# HeaterControl.net
KiCad netlist of a schematic drawn in EAGLE
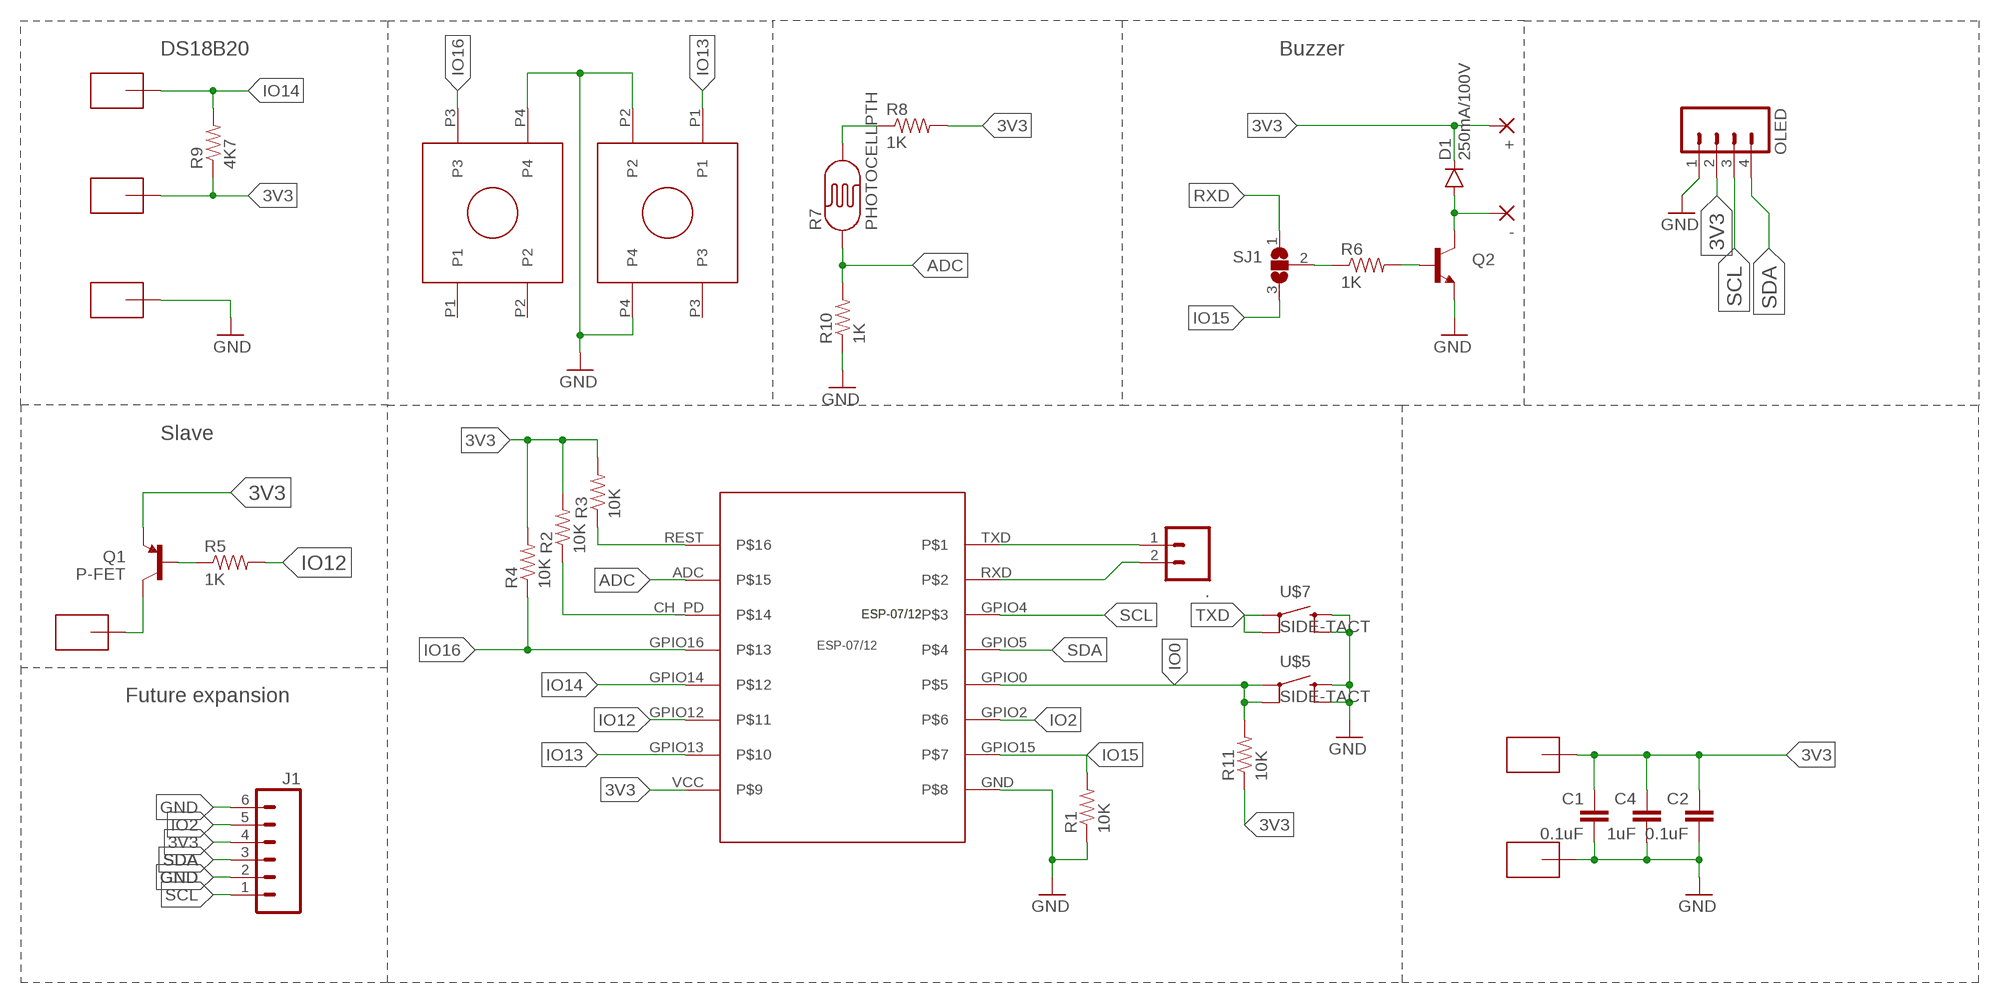
[diagram p0: schematic, sheet 1]

(export (version "E")
  (design (tool "Eeschema 10.0.6"))
  (components
    (comp (ref "+")
      (value "1,6/0,8")
      (footprint "eagle-import:1,6_0,8")
      (libsource (lib "eagle-import") (part "1,6/0,8"))
    )
    (comp (ref "-")
      (value "1,6/0,8")
      (footprint "eagle-import:1,6_0,8")
      (libsource (lib "eagle-import") (part "1,6/0,8"))
    )
    (comp (ref ".")
      (value "M02PTH")
      (footprint "eagle-import:1X02")
      (libsource (lib "eagle-import") (part "M02PTH"))
    )
    (comp (ref "C1")
      (value "0.1uF")
      (footprint "eagle-import:0805-CAP")
      (libsource (lib "eagle-import") (part "CAP"))
    )
    (comp (ref "C2")
      (value "0.1uF")
      (footprint "eagle-import:0805-CAP")
      (libsource (lib "eagle-import") (part "CAP"))
    )
    (comp (ref "C4")
      (value "1uF")
      (footprint "eagle-import:0805-CAP")
      (libsource (lib "eagle-import") (part "CAP"))
    )
    (comp (ref "D1")
      (value "250mA/100V")
      (footprint "eagle-import:SOD-323")
      (libsource (lib "eagle-import") (part "DIODEBAS16"))
    )
    (comp (ref "J1")
      (value "M06SILK_FEMALE_PTH")
      (footprint "eagle-import:1X06")
      (libsource (lib "eagle-import") (part "M06SILK_FEMALE_PTH"))
    )
    (comp (ref "LEFT")
      (value "OMROM_TH")
      (footprint "eagle-import:OMROM_TH")
      (libsource (lib "eagle-import") (part "OMROM_TH"))
    )
    (comp (ref "OLED")
      (value "M04PTH")
      (footprint "eagle-import:1X04")
      (libsource (lib "eagle-import") (part "M04PTH"))
    )
    (comp (ref "Q1")
      (value "P-FET")
      (footprint "eagle-import:SOT23-3")
      (libsource (lib "eagle-import") (part "TRANSISTOR_PNPSMD"))
    )
    (comp (ref "Q2")
      (value "TRANSISTOR_NPNSOT23-3")
      (footprint "eagle-import:SOT23-3")
      (libsource (lib "eagle-import") (part "TRANSISTOR_NPNSOT23-3"))
    )
    (comp (ref "R1")
      (value "10K")
      (footprint "eagle-import:0805")
      (libsource (lib "eagle-import") (part "RESISTOR0805-RES"))
    )
    (comp (ref "R2")
      (value "10K")
      (footprint "eagle-import:0805")
      (libsource (lib "eagle-import") (part "RESISTOR0805-RES"))
    )
    (comp (ref "R3")
      (value "10K")
      (footprint "eagle-import:0805")
      (libsource (lib "eagle-import") (part "RESISTOR0805-RES"))
    )
    (comp (ref "R4")
      (value "10K")
      (footprint "eagle-import:0805")
      (libsource (lib "eagle-import") (part "RESISTOR0805-RES"))
    )
    (comp (ref "R5")
      (value "1K")
      (footprint "eagle-import:0805")
      (libsource (lib "eagle-import") (part "RESISTOR0805-RES"))
    )
    (comp (ref "R6")
      (value "1K")
      (footprint "eagle-import:0805")
      (libsource (lib "eagle-import") (part "RESISTOR0805-RES"))
    )
    (comp (ref "R7")
      (value "PHOTOCELLPTH")
      (footprint "eagle-import:PHOTOCELL")
      (libsource (lib "eagle-import") (part "PHOTOCELLPTH"))
    )
    (comp (ref "R8")
      (value "1K")
      (footprint "eagle-import:0805")
      (libsource (lib "eagle-import") (part "RESISTOR0805-RES"))
    )
    (comp (ref "R9")
      (value "4K7")
      (footprint "eagle-import:0805")
      (libsource (lib "eagle-import") (part "RESISTOR0805-RES"))
    )
    (comp (ref "R10")
      (value "1K")
      (footprint "eagle-import:0805")
      (libsource (lib "eagle-import") (part "RESISTOR0805-RES"))
    )
    (comp (ref "R11")
      (value "10K")
      (footprint "eagle-import:0805")
      (libsource (lib "eagle-import") (part "RESISTOR0805-RES"))
    )
    (comp (ref "RIGHT")
      (value "OMROM_TH")
      (footprint "eagle-import:OMROM_TH")
      (libsource (lib "eagle-import") (part "OMROM_TH"))
    )
    (comp (ref "SJ1")
      (value "SJ2W")
      (footprint "eagle-import:SJ_2")
      (libsource (lib "eagle-import") (part "SJ2W"))
    )
    (comp (ref "U$1")
      (value "ESP-07/12")
      (footprint "eagle-import:ESP-07_12")
      (libsource (lib "eagle-import") (part "ESP-07/12"))
    )
    (comp (ref "U$2")
      (value "SMD-PAD1")
      (footprint "eagle-import:SMD-PAD1")
      (libsource (lib "eagle-import") (part "SMD-PAD1"))
    )
    (comp (ref "U$3")
      (value "SMD-PAD1")
      (footprint "eagle-import:SMD-PAD1")
      (libsource (lib "eagle-import") (part "SMD-PAD1"))
    )
    (comp (ref "U$5")
      (value "SIDE-TACT")
      (footprint "eagle-import:SIDE-TACT")
      (libsource (lib "eagle-import") (part "SIDE-TACT"))
    )
    (comp (ref "U$6")
      (value "SMD-PAD1")
      (footprint "eagle-import:SMD-PAD1")
      (libsource (lib "eagle-import") (part "SMD-PAD1"))
    )
    (comp (ref "U$7")
      (value "SIDE-TACT")
      (footprint "eagle-import:SIDE-TACT")
      (libsource (lib "eagle-import") (part "SIDE-TACT"))
    )
    (comp (ref "U$8")
      (value "SMD-PAD1")
      (footprint "eagle-import:SMD-PAD1")
      (libsource (lib "eagle-import") (part "SMD-PAD1"))
    )
    (comp (ref "U$10")
      (value "SMD-PAD1")
      (footprint "eagle-import:SMD-PAD1")
      (libsource (lib "eagle-import") (part "SMD-PAD1"))
    )
    (comp (ref "U$11")
      (value "SMD-PAD1")
      (footprint "eagle-import:SMD-PAD1")
      (libsource (lib "eagle-import") (part "SMD-PAD1"))
    )
  )
  (nets
    (net (code "1") (name "3V3") (class "Default")
      (node (ref "+") (pin "1") (pinfunction "P_1") (pintype "passive"))
      (node (ref "C1") (pin "1") (pinfunction "1_1") (pintype "passive"))
      (node (ref "C2") (pin "1") (pinfunction "1_1") (pintype "passive"))
      (node (ref "C4") (pin "1") (pinfunction "1_1") (pintype "passive"))
      (node (ref "D1") (pin "C") (pinfunction "C_C") (pintype "passive"))
      (node (ref "J1") (pin "4") (pinfunction "4_4") (pintype "passive"))
      (node (ref "OLED") (pin "2") (pinfunction "2_2") (pintype "passive"))
      (node (ref "Q1") (pin "2") (pinfunction "E_2") (pintype "passive"))
      (node (ref "R11") (pin "1") (pinfunction "1_1") (pintype "passive"))
      (node (ref "R2") (pin "2") (pinfunction "2_2") (pintype "passive"))
      (node (ref "R3") (pin "2") (pinfunction "2_2") (pintype "passive"))
      (node (ref "R4") (pin "2") (pinfunction "2_2") (pintype "passive"))
      (node (ref "R8") (pin "2") (pinfunction "2_2") (pintype "passive"))
      (node (ref "R9") (pin "1") (pinfunction "1_1") (pintype "passive"))
      (node (ref "U$1") (pin "VCC") (pinfunction "P$9_VCC") (pintype "bidirectional"))
      (node (ref "U$3") (pin ">NAME") (pinfunction "P$1_>NAME") (pintype "bidirectional"))
      (node (ref "U$8") (pin ">NAME") (pinfunction "P$1_>NAME") (pintype "bidirectional"))
    )
    (net (code "2") (name "ADC") (class "Default")
      (node (ref "R10") (pin "2") (pinfunction "2_2") (pintype "passive"))
      (node (ref "R7") (pin "1") (pinfunction "P$1_1") (pintype "bidirectional"))
      (node (ref "U$1") (pin "ADC") (pinfunction "P$15_ADC") (pintype "bidirectional"))
    )
    (net (code "3") (name "GND") (class "Default")
      (node (ref "C1") (pin "2") (pinfunction "2_2") (pintype "passive"))
      (node (ref "C2") (pin "2") (pinfunction "2_2") (pintype "passive"))
      (node (ref "C4") (pin "2") (pinfunction "2_2") (pintype "passive"))
      (node (ref "J1") (pin "2") (pinfunction "2_2") (pintype "passive"))
      (node (ref "J1") (pin "6") (pinfunction "6_6") (pintype "passive"))
      (node (ref "LEFT") (pin "P4") (pinfunction "P4_P4") (pintype "bidirectional"))
      (node (ref "OLED") (pin "1") (pinfunction "1_1") (pintype "passive"))
      (node (ref "Q2") (pin "2") (pinfunction "E_2") (pintype "passive"))
      (node (ref "R1") (pin "1") (pinfunction "1_1") (pintype "passive"))
      (node (ref "R10") (pin "1") (pinfunction "1_1") (pintype "passive"))
      (node (ref "RIGHT") (pin "P2") (pinfunction "P2_P2") (pintype "bidirectional"))
      (node (ref "RIGHT") (pin "P4") (pinfunction "P4_P4") (pintype "bidirectional"))
      (node (ref "U$1") (pin "GND") (pinfunction "P$8_GND") (pintype "bidirectional"))
      (node (ref "U$11") (pin ">NAME") (pinfunction "P$1_>NAME") (pintype "bidirectional"))
      (node (ref "U$5") (pin "3") (pinfunction "2_3") (pintype "passive"))
      (node (ref "U$5") (pin "4") (pinfunction "4_4") (pintype "passive"))
      (node (ref "U$6") (pin ">NAME") (pinfunction "P$1_>NAME") (pintype "bidirectional"))
      (node (ref "U$7") (pin "3") (pinfunction "2_3") (pintype "passive"))
      (node (ref "U$7") (pin "4") (pinfunction "4_4") (pintype "passive"))
    )
    (net (code "4") (name "IO0") (class "Default")
      (node (ref "R11") (pin "2") (pinfunction "2_2") (pintype "passive"))
      (node (ref "U$1") (pin "GPIO0") (pinfunction "P$5_GPIO0") (pintype "bidirectional"))
      (node (ref "U$5") (pin "1") (pinfunction "1_1") (pintype "passive"))
      (node (ref "U$5") (pin "2") (pinfunction "3_2") (pintype "passive"))
    )
    (net (code "5") (name "IO2") (class "Default")
      (node (ref "J1") (pin "5") (pinfunction "5_5") (pintype "passive"))
      (node (ref "U$1") (pin "GPIO2") (pinfunction "P$6_GPIO2") (pintype "bidirectional"))
    )
    (net (code "6") (name "IO12") (class "Default")
      (node (ref "R5") (pin "2") (pinfunction "2_2") (pintype "passive"))
      (node (ref "U$1") (pin "GPIO12") (pinfunction "P$11_GPIO12") (pintype "bidirectional"))
    )
    (net (code "7") (name "IO13") (class "Default")
      (node (ref "RIGHT") (pin "P1") (pinfunction "P1_P1") (pintype "bidirectional"))
      (node (ref "U$1") (pin "GPIO13") (pinfunction "P$10_GPIO13") (pintype "bidirectional"))
    )
    (net (code "8") (name "IO14") (class "Default")
      (node (ref "R9") (pin "2") (pinfunction "2_2") (pintype "passive"))
      (node (ref "U$1") (pin "GPIO14") (pinfunction "P$12_GPIO14") (pintype "bidirectional"))
      (node (ref "U$10") (pin ">NAME") (pinfunction "P$1_>NAME") (pintype "bidirectional"))
    )
    (net (code "9") (name "IO15") (class "Default")
      (node (ref "R1") (pin "2") (pinfunction "2_2") (pintype "passive"))
      (node (ref "SJ1") (pin "3") (pinfunction "3_3") (pintype "passive"))
      (node (ref "U$1") (pin "GPIO15") (pinfunction "P$7_GPIO15") (pintype "bidirectional"))
    )
    (net (code "10") (name "IO16") (class "Default")
      (node (ref "LEFT") (pin "P3") (pinfunction "P3_P3") (pintype "bidirectional"))
      (node (ref "R4") (pin "1") (pinfunction "1_1") (pintype "passive"))
      (node (ref "U$1") (pin "GPIO16") (pinfunction "P$13_GPIO16") (pintype "bidirectional"))
    )
    (net (code "11") (name "Net-(--P)") (class "Default")
      (node (ref "-") (pin "1") (pinfunction "P_1") (pintype "passive"))
      (node (ref "D1") (pin "A") (pinfunction "A_A") (pintype "passive"))
      (node (ref "Q2") (pin "3") (pinfunction "C_3") (pintype "passive"))
    )
    (net (code "12") (name "Net-(Q1-B)") (class "Default")
      (node (ref "Q1") (pin "1") (pinfunction "B_1") (pintype "passive"))
      (node (ref "R5") (pin "1") (pinfunction "1_1") (pintype "passive"))
    )
    (net (code "13") (name "Net-(Q1-C)") (class "Default")
      (node (ref "Q1") (pin "3") (pinfunction "C_3") (pintype "passive"))
      (node (ref "U$2") (pin ">NAME") (pinfunction "P$1_>NAME") (pintype "bidirectional"))
    )
    (net (code "14") (name "Net-(Q2-B)") (class "Default")
      (node (ref "Q2") (pin "1") (pinfunction "B_1") (pintype "passive"))
      (node (ref "R6") (pin "2") (pinfunction "2_2") (pintype "passive"))
    )
    (net (code "15") (name "Net-(R6-Pad1)") (class "Default")
      (node (ref "R6") (pin "1") (pinfunction "1_1") (pintype "passive"))
      (node (ref "SJ1") (pin "2") (pinfunction "2_2") (pintype "passive"))
    )
    (net (code "16") (name "Net-(R7-P$2)") (class "Default")
      (node (ref "R7") (pin "2") (pinfunction "P$2_2") (pintype "bidirectional"))
      (node (ref "R8") (pin "1") (pinfunction "1_1") (pintype "passive"))
    )
    (net (code "17") (name "Net-(U$1-P$14)") (class "Default")
      (node (ref "R2") (pin "1") (pinfunction "1_1") (pintype "passive"))
      (node (ref "U$1") (pin "CH_PD") (pinfunction "P$14_CH_PD") (pintype "bidirectional"))
    )
    (net (code "18") (name "Net-(U$1-P$16)") (class "Default")
      (node (ref "R3") (pin "1") (pinfunction "1_1") (pintype "passive"))
      (node (ref "U$1") (pin "REST") (pinfunction "P$16_REST") (pintype "bidirectional"))
    )
    (net (code "19") (name "RXD") (class "Default")
      (node (ref ".") (pin "2") (pinfunction "2_2") (pintype "passive"))
      (node (ref "SJ1") (pin "1") (pinfunction "1_1") (pintype "passive"))
      (node (ref "U$1") (pin "RXD") (pinfunction "P$2_RXD") (pintype "bidirectional"))
    )
    (net (code "20") (name "SCL") (class "Default")
      (node (ref "J1") (pin "1") (pinfunction "1_1") (pintype "passive"))
      (node (ref "OLED") (pin "3") (pinfunction "3_3") (pintype "passive"))
      (node (ref "U$1") (pin "GPIO4") (pinfunction "P$3_GPIO4") (pintype "bidirectional"))
    )
    (net (code "21") (name "SDA") (class "Default")
      (node (ref "J1") (pin "3") (pinfunction "3_3") (pintype "passive"))
      (node (ref "OLED") (pin "4") (pinfunction "4_4") (pintype "passive"))
      (node (ref "U$1") (pin "GPIO5") (pinfunction "P$4_GPIO5") (pintype "bidirectional"))
    )
    (net (code "22") (name "TXD") (class "Default")
      (node (ref ".") (pin "1") (pinfunction "1_1") (pintype "passive"))
      (node (ref "U$1") (pin "TXD") (pinfunction "P$1_TXD") (pintype "bidirectional"))
      (node (ref "U$7") (pin "1") (pinfunction "1_1") (pintype "passive"))
      (node (ref "U$7") (pin "2") (pinfunction "3_2") (pintype "passive"))
    )
    (net (code "23") (name "unconnected-(LEFT-PadP1)") (class "Default")
      (node (ref "LEFT") (pin "P1") (pinfunction "P1_P1") (pintype "bidirectional"))
    )
    (net (code "24") (name "unconnected-(LEFT-PadP2)") (class "Default")
      (node (ref "LEFT") (pin "P2") (pinfunction "P2_P2") (pintype "bidirectional"))
    )
    (net (code "25") (name "unconnected-(RIGHT-PadP3)") (class "Default")
      (node (ref "RIGHT") (pin "P3") (pinfunction "P3_P3") (pintype "bidirectional"))
    )
  )
)
